# Sheet1.net
KiCad netlist of a schematic drawn in Altium Designer
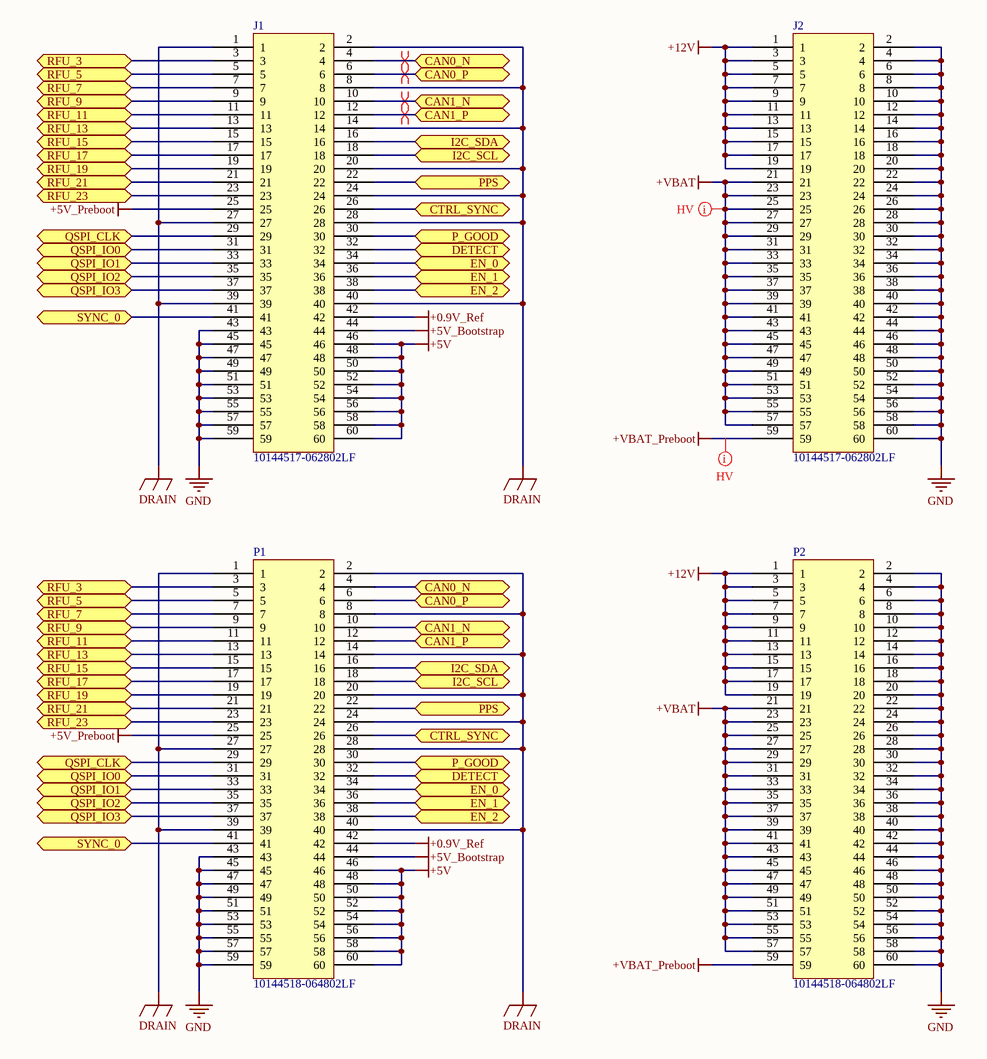
[diagram p0: Sheet1.SchDoc]

(export (version "E")
  (design (tool "Eeschema 10.0.6"))
  (components
    (comp (ref "J1")
      (value "10144517-062802LF")
      (footprint "10144517-062802LF")
      (libsource (lib "ModularPayload") (part "10144517-062802LF"))
    )
    (comp (ref "J2")
      (value "10144517-062802LF")
      (footprint "10144517-062802LF")
      (libsource (lib "ModularPayload") (part "10144517-062802LF"))
    )
    (comp (ref "P1")
      (value "10144518-064802LF")
      (footprint "10144518-064802LF")
      (libsource (lib "ModularPayload") (part "10144518-064802LF"))
    )
    (comp (ref "P2")
      (value "10144518-064802LF")
      (footprint "10144518-064802LF")
      (libsource (lib "ModularPayload") (part "10144518-064802LF"))
    )
  )
  (nets
    (net (code "1") (name "+0.9V_Ref") (class "Default")
      (node (ref "J1") (pin "42") (pinfunction "42_42") (pintype "passive"))
      (node (ref "P1") (pin "42") (pinfunction "42_42") (pintype "passive"))
    )
    (net (code "2") (name "+5V") (class "Default")
      (node (ref "J1") (pin "46") (pinfunction "46_46") (pintype "passive"))
      (node (ref "J1") (pin "48") (pinfunction "48_48") (pintype "passive"))
      (node (ref "J1") (pin "50") (pinfunction "50_50") (pintype "passive"))
      (node (ref "J1") (pin "52") (pinfunction "52_52") (pintype "passive"))
      (node (ref "J1") (pin "54") (pinfunction "54_54") (pintype "passive"))
      (node (ref "J1") (pin "56") (pinfunction "56_56") (pintype "passive"))
      (node (ref "J1") (pin "58") (pinfunction "58_58") (pintype "passive"))
      (node (ref "J1") (pin "60") (pinfunction "60_60") (pintype "passive"))
      (node (ref "P1") (pin "46") (pinfunction "46_46") (pintype "passive"))
      (node (ref "P1") (pin "48") (pinfunction "48_48") (pintype "passive"))
      (node (ref "P1") (pin "50") (pinfunction "50_50") (pintype "passive"))
      (node (ref "P1") (pin "52") (pinfunction "52_52") (pintype "passive"))
      (node (ref "P1") (pin "54") (pinfunction "54_54") (pintype "passive"))
      (node (ref "P1") (pin "56") (pinfunction "56_56") (pintype "passive"))
      (node (ref "P1") (pin "58") (pinfunction "58_58") (pintype "passive"))
      (node (ref "P1") (pin "60") (pinfunction "60_60") (pintype "passive"))
    )
    (net (code "3") (name "+5V_Bootstrap") (class "Default")
      (node (ref "J1") (pin "44") (pinfunction "44_44") (pintype "passive"))
      (node (ref "P1") (pin "44") (pinfunction "44_44") (pintype "passive"))
    )
    (net (code "4") (name "+5V_Preboot") (class "Default")
      (node (ref "J1") (pin "25") (pinfunction "25_25") (pintype "passive"))
      (node (ref "P1") (pin "25") (pinfunction "25_25") (pintype "passive"))
    )
    (net (code "5") (name "+12V") (class "Default")
      (node (ref "J2") (pin "1") (pinfunction "1_1") (pintype "passive"))
      (node (ref "J2") (pin "11") (pinfunction "11_11") (pintype "passive"))
      (node (ref "J2") (pin "13") (pinfunction "13_13") (pintype "passive"))
      (node (ref "J2") (pin "15") (pinfunction "15_15") (pintype "passive"))
      (node (ref "J2") (pin "17") (pinfunction "17_17") (pintype "passive"))
      (node (ref "J2") (pin "19") (pinfunction "19_19") (pintype "passive"))
      (node (ref "J2") (pin "3") (pinfunction "3_3") (pintype "passive"))
      (node (ref "J2") (pin "5") (pinfunction "5_5") (pintype "passive"))
      (node (ref "J2") (pin "7") (pinfunction "7_7") (pintype "passive"))
      (node (ref "J2") (pin "9") (pinfunction "9_9") (pintype "passive"))
      (node (ref "P2") (pin "1") (pinfunction "1_1") (pintype "passive"))
      (node (ref "P2") (pin "11") (pinfunction "11_11") (pintype "passive"))
      (node (ref "P2") (pin "13") (pinfunction "13_13") (pintype "passive"))
      (node (ref "P2") (pin "15") (pinfunction "15_15") (pintype "passive"))
      (node (ref "P2") (pin "17") (pinfunction "17_17") (pintype "passive"))
      (node (ref "P2") (pin "19") (pinfunction "19_19") (pintype "passive"))
      (node (ref "P2") (pin "3") (pinfunction "3_3") (pintype "passive"))
      (node (ref "P2") (pin "5") (pinfunction "5_5") (pintype "passive"))
      (node (ref "P2") (pin "7") (pinfunction "7_7") (pintype "passive"))
      (node (ref "P2") (pin "9") (pinfunction "9_9") (pintype "passive"))
    )
    (net (code "6") (name "+VBAT") (class "Default")
      (node (ref "J2") (pin "21") (pinfunction "21_21") (pintype "passive"))
      (node (ref "J2") (pin "23") (pinfunction "23_23") (pintype "passive"))
      (node (ref "J2") (pin "25") (pinfunction "25_25") (pintype "passive"))
      (node (ref "J2") (pin "27") (pinfunction "27_27") (pintype "passive"))
      (node (ref "J2") (pin "29") (pinfunction "29_29") (pintype "passive"))
      (node (ref "J2") (pin "31") (pinfunction "31_31") (pintype "passive"))
      (node (ref "J2") (pin "33") (pinfunction "33_33") (pintype "passive"))
      (node (ref "J2") (pin "35") (pinfunction "35_35") (pintype "passive"))
      (node (ref "J2") (pin "37") (pinfunction "37_37") (pintype "passive"))
      (node (ref "J2") (pin "39") (pinfunction "39_39") (pintype "passive"))
      (node (ref "J2") (pin "41") (pinfunction "41_41") (pintype "passive"))
      (node (ref "J2") (pin "43") (pinfunction "43_43") (pintype "passive"))
      (node (ref "J2") (pin "45") (pinfunction "45_45") (pintype "passive"))
      (node (ref "J2") (pin "47") (pinfunction "47_47") (pintype "passive"))
      (node (ref "J2") (pin "49") (pinfunction "49_49") (pintype "passive"))
      (node (ref "J2") (pin "51") (pinfunction "51_51") (pintype "passive"))
      (node (ref "J2") (pin "53") (pinfunction "53_53") (pintype "passive"))
      (node (ref "J2") (pin "55") (pinfunction "55_55") (pintype "passive"))
      (node (ref "J2") (pin "57") (pinfunction "57_57") (pintype "passive"))
      (node (ref "P2") (pin "21") (pinfunction "21_21") (pintype "passive"))
      (node (ref "P2") (pin "23") (pinfunction "23_23") (pintype "passive"))
      (node (ref "P2") (pin "25") (pinfunction "25_25") (pintype "passive"))
      (node (ref "P2") (pin "27") (pinfunction "27_27") (pintype "passive"))
      (node (ref "P2") (pin "29") (pinfunction "29_29") (pintype "passive"))
      (node (ref "P2") (pin "31") (pinfunction "31_31") (pintype "passive"))
      (node (ref "P2") (pin "33") (pinfunction "33_33") (pintype "passive"))
      (node (ref "P2") (pin "35") (pinfunction "35_35") (pintype "passive"))
      (node (ref "P2") (pin "37") (pinfunction "37_37") (pintype "passive"))
      (node (ref "P2") (pin "39") (pinfunction "39_39") (pintype "passive"))
      (node (ref "P2") (pin "41") (pinfunction "41_41") (pintype "passive"))
      (node (ref "P2") (pin "43") (pinfunction "43_43") (pintype "passive"))
      (node (ref "P2") (pin "45") (pinfunction "45_45") (pintype "passive"))
      (node (ref "P2") (pin "47") (pinfunction "47_47") (pintype "passive"))
      (node (ref "P2") (pin "49") (pinfunction "49_49") (pintype "passive"))
      (node (ref "P2") (pin "51") (pinfunction "51_51") (pintype "passive"))
      (node (ref "P2") (pin "53") (pinfunction "53_53") (pintype "passive"))
      (node (ref "P2") (pin "55") (pinfunction "55_55") (pintype "passive"))
      (node (ref "P2") (pin "57") (pinfunction "57_57") (pintype "passive"))
    )
    (net (code "7") (name "+VBAT_Preboot") (class "Default")
      (node (ref "J2") (pin "59") (pinfunction "59_59") (pintype "passive"))
      (node (ref "P2") (pin "59") (pinfunction "59_59") (pintype "passive"))
    )
    (net (code "8") (name "/CAN0_N") (class "Default")
      (node (ref "J1") (pin "4") (pinfunction "4_4") (pintype "passive"))
      (node (ref "P1") (pin "4") (pinfunction "4_4") (pintype "passive"))
    )
    (net (code "9") (name "/CAN0_P") (class "Default")
      (node (ref "J1") (pin "6") (pinfunction "6_6") (pintype "passive"))
      (node (ref "P1") (pin "6") (pinfunction "6_6") (pintype "passive"))
    )
    (net (code "10") (name "/CAN1_N") (class "Default")
      (node (ref "J1") (pin "10") (pinfunction "10_10") (pintype "passive"))
      (node (ref "P1") (pin "10") (pinfunction "10_10") (pintype "passive"))
    )
    (net (code "11") (name "/CAN1_P") (class "Default")
      (node (ref "J1") (pin "12") (pinfunction "12_12") (pintype "passive"))
      (node (ref "P1") (pin "12") (pinfunction "12_12") (pintype "passive"))
    )
    (net (code "12") (name "/CTRL_SYNC") (class "Default")
      (node (ref "J1") (pin "26") (pinfunction "26_26") (pintype "passive"))
      (node (ref "P1") (pin "26") (pinfunction "26_26") (pintype "passive"))
    )
    (net (code "13") (name "/DETECT") (class "Default")
      (node (ref "J1") (pin "32") (pinfunction "32_32") (pintype "passive"))
      (node (ref "P1") (pin "32") (pinfunction "32_32") (pintype "passive"))
    )
    (net (code "14") (name "/EN_0") (class "Default")
      (node (ref "J1") (pin "34") (pinfunction "34_34") (pintype "passive"))
      (node (ref "P1") (pin "34") (pinfunction "34_34") (pintype "passive"))
    )
    (net (code "15") (name "/EN_1") (class "Default")
      (node (ref "J1") (pin "36") (pinfunction "36_36") (pintype "passive"))
      (node (ref "P1") (pin "36") (pinfunction "36_36") (pintype "passive"))
    )
    (net (code "16") (name "/EN_2") (class "Default")
      (node (ref "J1") (pin "38") (pinfunction "38_38") (pintype "passive"))
      (node (ref "P1") (pin "38") (pinfunction "38_38") (pintype "passive"))
    )
    (net (code "17") (name "/I2C_SCL") (class "Default")
      (node (ref "J1") (pin "18") (pinfunction "18_18") (pintype "passive"))
      (node (ref "P1") (pin "18") (pinfunction "18_18") (pintype "passive"))
    )
    (net (code "18") (name "/I2C_SDA") (class "Default")
      (node (ref "J1") (pin "16") (pinfunction "16_16") (pintype "passive"))
      (node (ref "P1") (pin "16") (pinfunction "16_16") (pintype "passive"))
    )
    (net (code "19") (name "/PPS") (class "Default")
      (node (ref "J1") (pin "22") (pinfunction "22_22") (pintype "passive"))
      (node (ref "P1") (pin "22") (pinfunction "22_22") (pintype "passive"))
    )
    (net (code "20") (name "/P_GOOD") (class "Default")
      (node (ref "J1") (pin "30") (pinfunction "30_30") (pintype "passive"))
      (node (ref "P1") (pin "30") (pinfunction "30_30") (pintype "passive"))
    )
    (net (code "21") (name "/QSPI_CLK") (class "Default")
      (node (ref "J1") (pin "29") (pinfunction "29_29") (pintype "passive"))
      (node (ref "P1") (pin "29") (pinfunction "29_29") (pintype "passive"))
    )
    (net (code "22") (name "/QSPI_IO0") (class "Default")
      (node (ref "J1") (pin "31") (pinfunction "31_31") (pintype "passive"))
      (node (ref "P1") (pin "31") (pinfunction "31_31") (pintype "passive"))
    )
    (net (code "23") (name "/QSPI_IO1") (class "Default")
      (node (ref "J1") (pin "33") (pinfunction "33_33") (pintype "passive"))
      (node (ref "P1") (pin "33") (pinfunction "33_33") (pintype "passive"))
    )
    (net (code "24") (name "/QSPI_IO2") (class "Default")
      (node (ref "J1") (pin "35") (pinfunction "35_35") (pintype "passive"))
      (node (ref "P1") (pin "35") (pinfunction "35_35") (pintype "passive"))
    )
    (net (code "25") (name "/QSPI_IO3") (class "Default")
      (node (ref "J1") (pin "37") (pinfunction "37_37") (pintype "passive"))
      (node (ref "P1") (pin "37") (pinfunction "37_37") (pintype "passive"))
    )
    (net (code "26") (name "/RFU_3") (class "Default")
      (node (ref "J1") (pin "3") (pinfunction "3_3") (pintype "passive"))
      (node (ref "P1") (pin "3") (pinfunction "3_3") (pintype "passive"))
    )
    (net (code "27") (name "/RFU_5") (class "Default")
      (node (ref "J1") (pin "5") (pinfunction "5_5") (pintype "passive"))
      (node (ref "P1") (pin "5") (pinfunction "5_5") (pintype "passive"))
    )
    (net (code "28") (name "/RFU_7") (class "Default")
      (node (ref "J1") (pin "7") (pinfunction "7_7") (pintype "passive"))
      (node (ref "P1") (pin "7") (pinfunction "7_7") (pintype "passive"))
    )
    (net (code "29") (name "/RFU_9") (class "Default")
      (node (ref "J1") (pin "9") (pinfunction "9_9") (pintype "passive"))
      (node (ref "P1") (pin "9") (pinfunction "9_9") (pintype "passive"))
    )
    (net (code "30") (name "/RFU_11") (class "Default")
      (node (ref "J1") (pin "11") (pinfunction "11_11") (pintype "passive"))
      (node (ref "P1") (pin "11") (pinfunction "11_11") (pintype "passive"))
    )
    (net (code "31") (name "/RFU_13") (class "Default")
      (node (ref "J1") (pin "13") (pinfunction "13_13") (pintype "passive"))
      (node (ref "P1") (pin "13") (pinfunction "13_13") (pintype "passive"))
    )
    (net (code "32") (name "/RFU_15") (class "Default")
      (node (ref "J1") (pin "15") (pinfunction "15_15") (pintype "passive"))
      (node (ref "P1") (pin "15") (pinfunction "15_15") (pintype "passive"))
    )
    (net (code "33") (name "/RFU_17") (class "Default")
      (node (ref "J1") (pin "17") (pinfunction "17_17") (pintype "passive"))
      (node (ref "P1") (pin "17") (pinfunction "17_17") (pintype "passive"))
    )
    (net (code "34") (name "/RFU_19") (class "Default")
      (node (ref "J1") (pin "19") (pinfunction "19_19") (pintype "passive"))
      (node (ref "P1") (pin "19") (pinfunction "19_19") (pintype "passive"))
    )
    (net (code "35") (name "/RFU_21") (class "Default")
      (node (ref "J1") (pin "21") (pinfunction "21_21") (pintype "passive"))
      (node (ref "P1") (pin "21") (pinfunction "21_21") (pintype "passive"))
    )
    (net (code "36") (name "/RFU_23") (class "Default")
      (node (ref "J1") (pin "23") (pinfunction "23_23") (pintype "passive"))
      (node (ref "P1") (pin "23") (pinfunction "23_23") (pintype "passive"))
    )
    (net (code "37") (name "/SYNC_0") (class "Default")
      (node (ref "J1") (pin "41") (pinfunction "41_41") (pintype "passive"))
      (node (ref "P1") (pin "41") (pinfunction "41_41") (pintype "passive"))
    )
    (net (code "38") (name "DRAIN") (class "Default")
      (node (ref "J1") (pin "1") (pinfunction "1_1") (pintype "passive"))
      (node (ref "J1") (pin "14") (pinfunction "14_14") (pintype "passive"))
      (node (ref "J1") (pin "2") (pinfunction "2_2") (pintype "passive"))
      (node (ref "J1") (pin "20") (pinfunction "20_20") (pintype "passive"))
      (node (ref "J1") (pin "24") (pinfunction "24_24") (pintype "passive"))
      (node (ref "J1") (pin "27") (pinfunction "27_27") (pintype "passive"))
      (node (ref "J1") (pin "28") (pinfunction "28_28") (pintype "passive"))
      (node (ref "J1") (pin "39") (pinfunction "39_39") (pintype "passive"))
      (node (ref "J1") (pin "40") (pinfunction "40_40") (pintype "passive"))
      (node (ref "J1") (pin "8") (pinfunction "8_8") (pintype "passive"))
      (node (ref "P1") (pin "1") (pinfunction "1_1") (pintype "passive"))
      (node (ref "P1") (pin "14") (pinfunction "14_14") (pintype "passive"))
      (node (ref "P1") (pin "2") (pinfunction "2_2") (pintype "passive"))
      (node (ref "P1") (pin "20") (pinfunction "20_20") (pintype "passive"))
      (node (ref "P1") (pin "24") (pinfunction "24_24") (pintype "passive"))
      (node (ref "P1") (pin "27") (pinfunction "27_27") (pintype "passive"))
      (node (ref "P1") (pin "28") (pinfunction "28_28") (pintype "passive"))
      (node (ref "P1") (pin "39") (pinfunction "39_39") (pintype "passive"))
      (node (ref "P1") (pin "40") (pinfunction "40_40") (pintype "passive"))
      (node (ref "P1") (pin "8") (pinfunction "8_8") (pintype "passive"))
    )
    (net (code "39") (name "GND") (class "Default")
      (node (ref "J1") (pin "43") (pinfunction "43_43") (pintype "passive"))
      (node (ref "J1") (pin "45") (pinfunction "45_45") (pintype "passive"))
      (node (ref "J1") (pin "47") (pinfunction "47_47") (pintype "passive"))
      (node (ref "J1") (pin "49") (pinfunction "49_49") (pintype "passive"))
      (node (ref "J1") (pin "51") (pinfunction "51_51") (pintype "passive"))
      (node (ref "J1") (pin "53") (pinfunction "53_53") (pintype "passive"))
      (node (ref "J1") (pin "55") (pinfunction "55_55") (pintype "passive"))
      (node (ref "J1") (pin "57") (pinfunction "57_57") (pintype "passive"))
      (node (ref "J1") (pin "59") (pinfunction "59_59") (pintype "passive"))
      (node (ref "J2") (pin "10") (pinfunction "10_10") (pintype "passive"))
      (node (ref "J2") (pin "12") (pinfunction "12_12") (pintype "passive"))
      (node (ref "J2") (pin "14") (pinfunction "14_14") (pintype "passive"))
      (node (ref "J2") (pin "16") (pinfunction "16_16") (pintype "passive"))
      (node (ref "J2") (pin "18") (pinfunction "18_18") (pintype "passive"))
      (node (ref "J2") (pin "2") (pinfunction "2_2") (pintype "passive"))
      (node (ref "J2") (pin "20") (pinfunction "20_20") (pintype "passive"))
      (node (ref "J2") (pin "22") (pinfunction "22_22") (pintype "passive"))
      (node (ref "J2") (pin "24") (pinfunction "24_24") (pintype "passive"))
      (node (ref "J2") (pin "26") (pinfunction "26_26") (pintype "passive"))
      (node (ref "J2") (pin "28") (pinfunction "28_28") (pintype "passive"))
      (node (ref "J2") (pin "30") (pinfunction "30_30") (pintype "passive"))
      (node (ref "J2") (pin "32") (pinfunction "32_32") (pintype "passive"))
      (node (ref "J2") (pin "34") (pinfunction "34_34") (pintype "passive"))
      (node (ref "J2") (pin "36") (pinfunction "36_36") (pintype "passive"))
      (node (ref "J2") (pin "38") (pinfunction "38_38") (pintype "passive"))
      (node (ref "J2") (pin "4") (pinfunction "4_4") (pintype "passive"))
      (node (ref "J2") (pin "40") (pinfunction "40_40") (pintype "passive"))
      (node (ref "J2") (pin "42") (pinfunction "42_42") (pintype "passive"))
      (node (ref "J2") (pin "44") (pinfunction "44_44") (pintype "passive"))
      (node (ref "J2") (pin "46") (pinfunction "46_46") (pintype "passive"))
      (node (ref "J2") (pin "48") (pinfunction "48_48") (pintype "passive"))
      (node (ref "J2") (pin "50") (pinfunction "50_50") (pintype "passive"))
      (node (ref "J2") (pin "52") (pinfunction "52_52") (pintype "passive"))
      (node (ref "J2") (pin "54") (pinfunction "54_54") (pintype "passive"))
      (node (ref "J2") (pin "56") (pinfunction "56_56") (pintype "passive"))
      (node (ref "J2") (pin "58") (pinfunction "58_58") (pintype "passive"))
      (node (ref "J2") (pin "6") (pinfunction "6_6") (pintype "passive"))
      (node (ref "J2") (pin "60") (pinfunction "60_60") (pintype "passive"))
      (node (ref "J2") (pin "8") (pinfunction "8_8") (pintype "passive"))
      (node (ref "P1") (pin "43") (pinfunction "43_43") (pintype "passive"))
      (node (ref "P1") (pin "45") (pinfunction "45_45") (pintype "passive"))
      (node (ref "P1") (pin "47") (pinfunction "47_47") (pintype "passive"))
      (node (ref "P1") (pin "49") (pinfunction "49_49") (pintype "passive"))
      (node (ref "P1") (pin "51") (pinfunction "51_51") (pintype "passive"))
      (node (ref "P1") (pin "53") (pinfunction "53_53") (pintype "passive"))
      (node (ref "P1") (pin "55") (pinfunction "55_55") (pintype "passive"))
      (node (ref "P1") (pin "57") (pinfunction "57_57") (pintype "passive"))
      (node (ref "P1") (pin "59") (pinfunction "59_59") (pintype "passive"))
      (node (ref "P2") (pin "10") (pinfunction "10_10") (pintype "passive"))
      (node (ref "P2") (pin "12") (pinfunction "12_12") (pintype "passive"))
      (node (ref "P2") (pin "14") (pinfunction "14_14") (pintype "passive"))
      (node (ref "P2") (pin "16") (pinfunction "16_16") (pintype "passive"))
      (node (ref "P2") (pin "18") (pinfunction "18_18") (pintype "passive"))
      (node (ref "P2") (pin "2") (pinfunction "2_2") (pintype "passive"))
      (node (ref "P2") (pin "20") (pinfunction "20_20") (pintype "passive"))
      (node (ref "P2") (pin "22") (pinfunction "22_22") (pintype "passive"))
      (node (ref "P2") (pin "24") (pinfunction "24_24") (pintype "passive"))
      (node (ref "P2") (pin "26") (pinfunction "26_26") (pintype "passive"))
      (node (ref "P2") (pin "28") (pinfunction "28_28") (pintype "passive"))
      (node (ref "P2") (pin "30") (pinfunction "30_30") (pintype "passive"))
      (node (ref "P2") (pin "32") (pinfunction "32_32") (pintype "passive"))
      (node (ref "P2") (pin "34") (pinfunction "34_34") (pintype "passive"))
      (node (ref "P2") (pin "36") (pinfunction "36_36") (pintype "passive"))
      (node (ref "P2") (pin "38") (pinfunction "38_38") (pintype "passive"))
      (node (ref "P2") (pin "4") (pinfunction "4_4") (pintype "passive"))
      (node (ref "P2") (pin "40") (pinfunction "40_40") (pintype "passive"))
      (node (ref "P2") (pin "42") (pinfunction "42_42") (pintype "passive"))
      (node (ref "P2") (pin "44") (pinfunction "44_44") (pintype "passive"))
      (node (ref "P2") (pin "46") (pinfunction "46_46") (pintype "passive"))
      (node (ref "P2") (pin "48") (pinfunction "48_48") (pintype "passive"))
      (node (ref "P2") (pin "50") (pinfunction "50_50") (pintype "passive"))
      (node (ref "P2") (pin "52") (pinfunction "52_52") (pintype "passive"))
      (node (ref "P2") (pin "54") (pinfunction "54_54") (pintype "passive"))
      (node (ref "P2") (pin "56") (pinfunction "56_56") (pintype "passive"))
      (node (ref "P2") (pin "58") (pinfunction "58_58") (pintype "passive"))
      (node (ref "P2") (pin "6") (pinfunction "6_6") (pintype "passive"))
      (node (ref "P2") (pin "60") (pinfunction "60_60") (pintype "passive"))
      (node (ref "P2") (pin "8") (pinfunction "8_8") (pintype "passive"))
    )
  )
)
